# esp3d_8266_r2.net
KiCad netlist of a schematic drawn in EAGLE
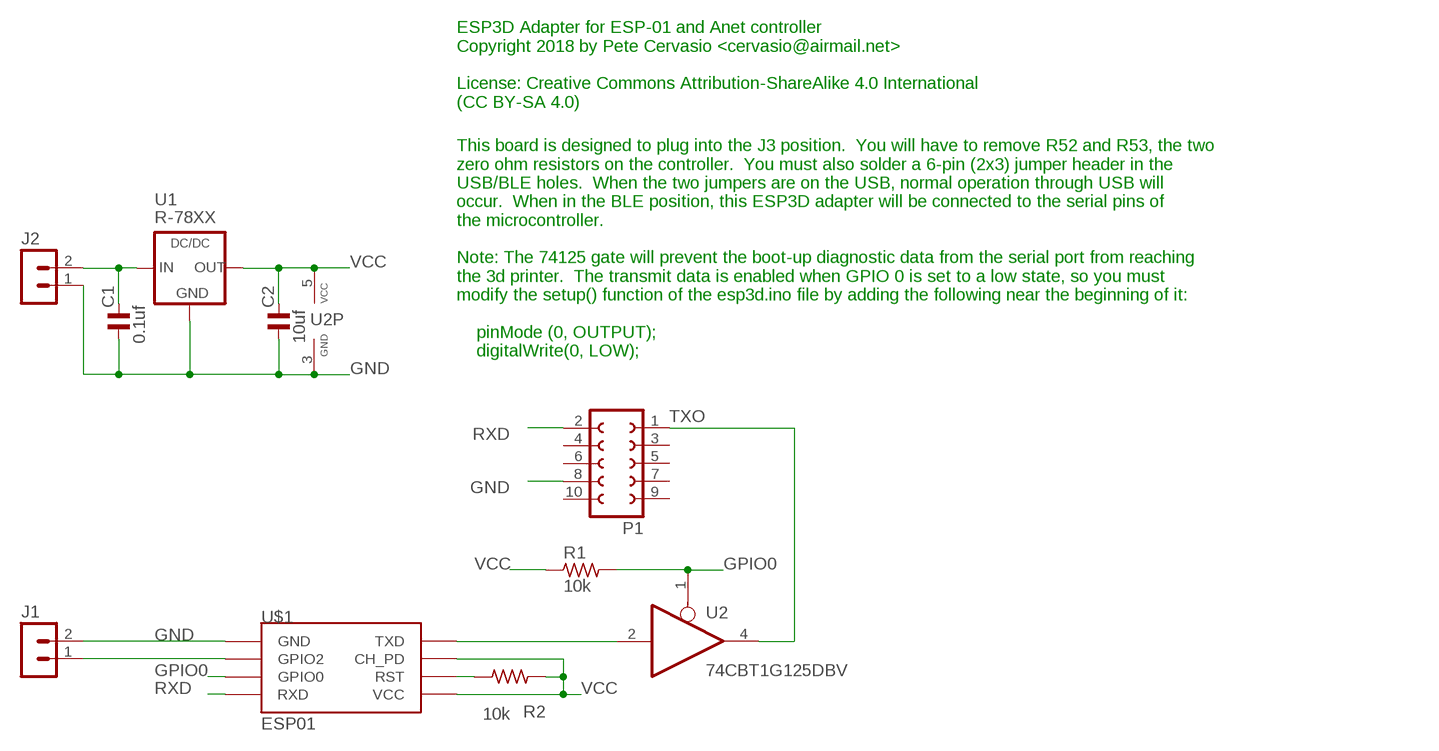
[diagram p0: schematic, sheet 1]

(export (version "E")
  (design (tool "Eeschema 10.0.6"))
  (components
    (comp (ref "C1")
      (value "0.1uf")
      (footprint "eagle-import:C0805")
      (libsource (lib "eagle-import") (part "C_0805"))
    )
    (comp (ref "C2")
      (value "10uf")
      (footprint "eagle-import:C0805")
      (libsource (lib "eagle-import") (part "C_0805"))
    )
    (comp (ref "J1")
      (value "MA02-1")
      (footprint "eagle-import:MA02-1")
      (libsource (lib "eagle-import") (part "MA02-1"))
    )
    (comp (ref "J2")
      (value "MA02-1")
      (footprint "eagle-import:MA02-1")
      (libsource (lib "eagle-import") (part "MA02-1"))
    )
    (comp (ref "P1")
      (value "FE05-2")
      (footprint "eagle-import:FE05-2")
      (libsource (lib "eagle-import") (part "FE05-2"))
    )
    (comp (ref "R1")
      (value "10k")
      (footprint "eagle-import:R0805")
      (libsource (lib "eagle-import") (part "R_0805"))
    )
    (comp (ref "R2")
      (value "10k")
      (footprint "eagle-import:R0805")
      (libsource (lib "eagle-import") (part "R_0805"))
    )
    (comp (ref "U$1")
      (value "ESP01")
      (footprint "eagle-import:ESP01")
      (libsource (lib "eagle-import") (part "ESP01"))
    )
    (comp (ref "U1")
      (value "R-78XX")
      (footprint "eagle-import:R-78XX")
      (libsource (lib "eagle-import") (part "R-78XX"))
    )
    (comp (ref "U2")
      (value "74CBT1G125DBV")
      (footprint "eagle-import:SOT23-5")
      (libsource (lib "eagle-import") (part "741G125DBVCBT"))
    )
  )
  (nets
    (net (code "1") (name "/GND") (class "Default")
      (node (ref "C1") (pin "1") (pinfunction "1_1") (pintype "passive"))
      (node (ref "C2") (pin "1") (pinfunction "1_1") (pintype "passive"))
      (node (ref "J1") (pin "2") (pinfunction "2_2") (pintype "passive"))
      (node (ref "J2") (pin "1") (pinfunction "1_1") (pintype "passive"))
      (node (ref "P1") (pin "8") (pinfunction "8_8") (pintype "passive"))
      (node (ref "U$1") (pin "GND") (pinfunction "GND_GND") (pintype "bidirectional"))
      (node (ref "U1") (pin "2") (pinfunction "GND_2") (pintype "input"))
      (node (ref "U2") (pin "3") (pinfunction "GND_3") (pintype "power_in"))
    )
    (net (code "2") (name "/GPIO0") (class "Default")
      (node (ref "R1") (pin "2") (pinfunction "2_2") (pintype "passive"))
      (node (ref "U$1") (pin "GPIO0") (pinfunction "GPIO0_GPIO0") (pintype "bidirectional"))
      (node (ref "U2") (pin "1") (pinfunction "OE_1") (pintype "input"))
    )
    (net (code "3") (name "/RXD") (class "Default")
      (node (ref "P1") (pin "2") (pinfunction "2_2") (pintype "passive"))
      (node (ref "U$1") (pin "RX") (pinfunction "RXD_RX") (pintype "bidirectional"))
    )
    (net (code "4") (name "/TXO") (class "Default")
      (node (ref "P1") (pin "1") (pinfunction "1_1") (pintype "passive"))
      (node (ref "U2") (pin "4") (pinfunction "O_4") (pintype "tri_state"))
    )
    (net (code "5") (name "/VCC") (class "Default")
      (node (ref "C2") (pin "2") (pinfunction "2_2") (pintype "passive"))
      (node (ref "R1") (pin "1") (pinfunction "1_1") (pintype "passive"))
      (node (ref "R2") (pin "1") (pinfunction "1_1") (pintype "passive"))
      (node (ref "U$1") (pin "CH_PD") (pinfunction "CH_PD_CH_PD") (pintype "bidirectional"))
      (node (ref "U$1") (pin "VCC") (pinfunction "VCC_VCC") (pintype "bidirectional"))
      (node (ref "U1") (pin "3") (pinfunction "OUT_3") (pintype "passive"))
      (node (ref "U2") (pin "5") (pinfunction "VCC_5") (pintype "power_in"))
    )
    (net (code "6") (name "Net-(J1-Pad1)") (class "Default")
      (node (ref "J1") (pin "1") (pinfunction "1_1") (pintype "passive"))
      (node (ref "U$1") (pin "GPIO2") (pinfunction "GPIO2_GPIO2") (pintype "bidirectional"))
    )
    (net (code "7") (name "Net-(R2-Pad2)") (class "Default")
      (node (ref "R2") (pin "2") (pinfunction "2_2") (pintype "passive"))
      (node (ref "U$1") (pin "RST") (pinfunction "RST_RST") (pintype "bidirectional"))
    )
    (net (code "8") (name "Net-(U$1-TXD)") (class "Default")
      (node (ref "U$1") (pin "TX") (pinfunction "TXD_TX") (pintype "bidirectional"))
      (node (ref "U2") (pin "2") (pinfunction "I_2") (pintype "input"))
    )
    (net (code "9") (name "Net-(U1-IN)") (class "Default")
      (node (ref "C1") (pin "2") (pinfunction "2_2") (pintype "passive"))
      (node (ref "J2") (pin "2") (pinfunction "2_2") (pintype "passive"))
      (node (ref "U1") (pin "1") (pinfunction "IN_1") (pintype "input"))
    )
    (net (code "10") (name "unconnected-(P1-Pad3)") (class "Default")
      (node (ref "P1") (pin "3") (pinfunction "3_3") (pintype "passive"))
    )
    (net (code "11") (name "unconnected-(P1-Pad4)") (class "Default")
      (node (ref "P1") (pin "4") (pinfunction "4_4") (pintype "passive"))
    )
    (net (code "12") (name "unconnected-(P1-Pad5)") (class "Default")
      (node (ref "P1") (pin "5") (pinfunction "5_5") (pintype "passive"))
    )
    (net (code "13") (name "unconnected-(P1-Pad6)") (class "Default")
      (node (ref "P1") (pin "6") (pinfunction "6_6") (pintype "passive"))
    )
    (net (code "14") (name "unconnected-(P1-Pad7)") (class "Default")
      (node (ref "P1") (pin "7") (pinfunction "7_7") (pintype "passive"))
    )
    (net (code "15") (name "unconnected-(P1-Pad9)") (class "Default")
      (node (ref "P1") (pin "9") (pinfunction "9_9") (pintype "passive"))
    )
    (net (code "16") (name "unconnected-(P1-Pad10)") (class "Default")
      (node (ref "P1") (pin "10") (pinfunction "10_10") (pintype "passive"))
    )
  )
)
